# ai.net
KiCad netlist of a schematic drawn in Altium Designer
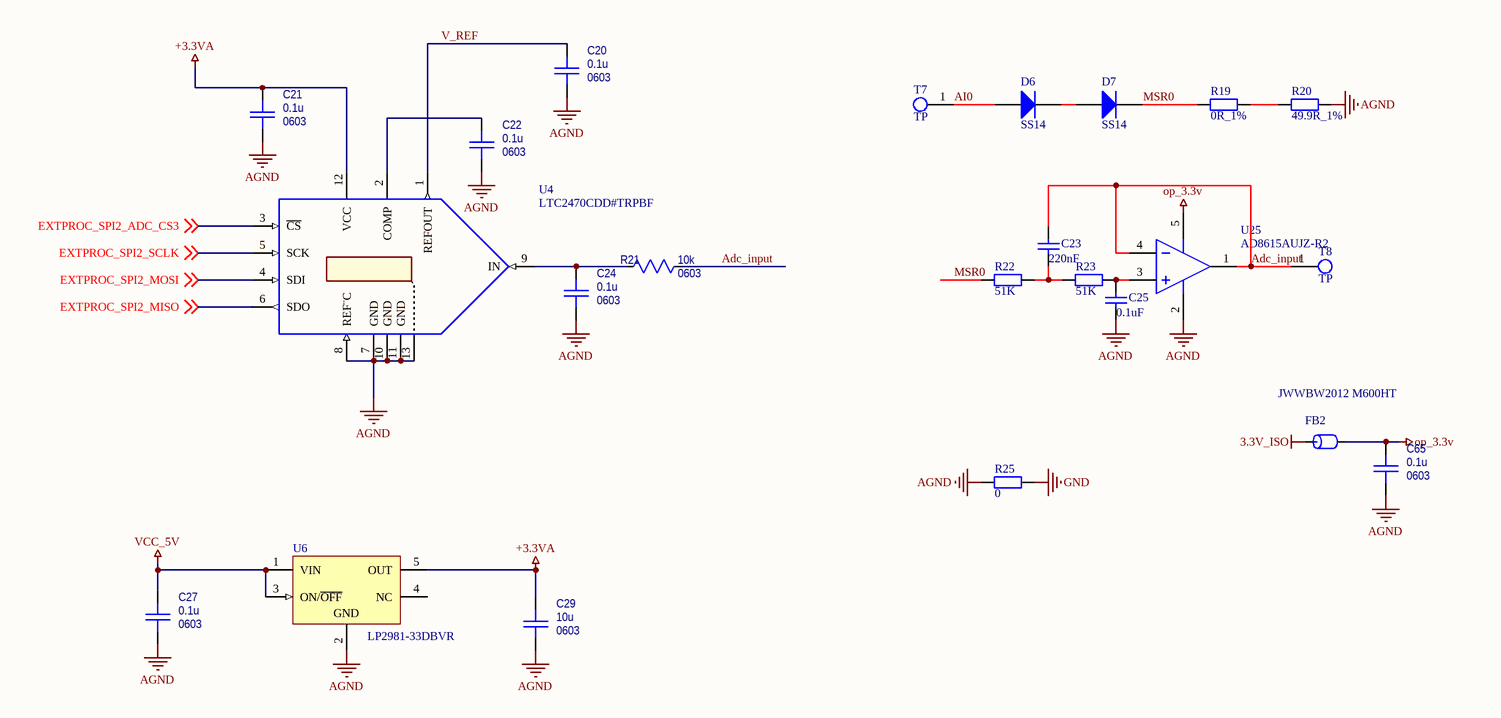
[diagram p0: ai.SchDoc]

(export (version "E")
  (design (tool "Eeschema 10.0.6"))
  (components
    (comp (ref "C20")
      (value "0.1u")
      (footprint "CAPC1608X092N_0603")
      (description "Capacitor, MLCC")
      (fields
        (field (name "PARTNUMBER") "C0603C104M5RACTU")
        (field (name "TOLERANCE") "[tol]")
        (field (name "PACKAGE") "0603")
      )
      (libsource (lib "Karl") (part "Capacitor_0603"))
    )
    (comp (ref "C21")
      (value "0.1u")
      (footprint "CAPC1608X092N_0603")
      (description "Capacitor, MLCC")
      (fields
        (field (name "PARTNUMBER") "C0603C104M5RACTU")
        (field (name "TOLERANCE") "[tol]")
        (field (name "PACKAGE") "0603")
      )
      (libsource (lib "Karl") (part "Capacitor_0603"))
    )
    (comp (ref "C22")
      (value "0.1u")
      (footprint "CAPC1608X092N_0603")
      (description "Capacitor, MLCC")
      (fields
        (field (name "PARTNUMBER") "C0603C104M5RACTU")
        (field (name "TOLERANCE") "[tol]")
        (field (name "PACKAGE") "0603")
      )
      (libsource (lib "Karl") (part "Capacitor_0603"))
    )
    (comp (ref "C23")
      (value "220nF")
      (footprint "0805C")
      (description "Capacitor")
      (fields (field (name "PUBLISHER") "Altium Limited"))
      (libsource (lib "Miscellaneous Devices") (part "Cap"))
    )
    (comp (ref "C24")
      (value "0.1u")
      (footprint "CAPC1608X092N_0603")
      (description "Capacitor, MLCC")
      (fields
        (field (name "PARTNUMBER") "C0603C104M5RACTU")
        (field (name "TOLERANCE") "[tol]")
        (field (name "PACKAGE") "0603")
      )
      (libsource (lib "Karl") (part "Capacitor_0603"))
    )
    (comp (ref "C25")
      (value "0.1uF")
      (footprint "0603C")
      (description "Capacitor")
      (fields (field (name "PUBLISHER") "Altium Limited"))
      (libsource (lib "Miscellaneous Devices") (part "Cap"))
    )
    (comp (ref "C27")
      (value "0.1u")
      (footprint "CAPC1608X092N_0603")
      (description "Capacitor, MLCC")
      (fields
        (field (name "PARTNUMBER") "C0603C104M5RACTU")
        (field (name "TOLERANCE") "[tol]")
        (field (name "PACKAGE") "0603")
      )
      (libsource (lib "Karl") (part "Capacitor_0603"))
    )
    (comp (ref "C29")
      (value "10u")
      (footprint "CAPC1608X092N_0603")
      (description "Capacitor, MLCC")
      (fields
        (field (name "PARTNUMBER") "GRM188R61A106KE69D")
        (field (name "TOLERANCE") "[tol]")
        (field (name "PACKAGE") "0603")
      )
      (libsource (lib "Karl") (part "Capacitor_0603"))
    )
    (comp (ref "C65")
      (value "0.1u")
      (footprint "CAPC1608X092N_0603")
      (description "Capacitor, MLCC")
      (fields
        (field (name "PARTNUMBER") "C0603C104M5RACTU")
        (field (name "TOLERANCE") "[tol]")
        (field (name "PACKAGE") "0603")
      )
      (libsource (lib "Karl") (part "Capacitor_0603"))
    )
    (comp (ref "D6")
      (value "SS14")
      (footprint "DO-214AC")
      (description "Default Diode")
      (fields (field (name "PUBLISHER") "Altium Limited"))
      (libsource (lib "Miscellaneous Devices") (part "Diode"))
    )
    (comp (ref "D7")
      (value "SS14")
      (footprint "DO-214AC")
      (description "Default Diode")
      (fields (field (name "PUBLISHER") "Altium Limited"))
      (libsource (lib "Miscellaneous Devices") (part "Diode"))
    )
    (comp (ref "FB2")
      (value "JWWBW2012 M600HT")
      (footprint "0805R")
      (libsource (lib "Schlib_20110825") (part "FB"))
    )
    (comp (ref "R19") (value "0R_1%") (footprint "0805R") (libsource (lib "MQlibrary") (part "Res0805M")))
    (comp (ref "R20") (value "49.9R_1%") (footprint "0805R") (libsource (lib "MQlibrary") (part "Res0805M")))
    (comp (ref "R21")
      (value "10k")
      (footprint "RESC1608X055N_0603")
      (description "Resistor, Standard")
      (fields
        (field (name "PARTNUMBER") "RR0816P-103-D")
        (field (name "TOLERANCE") "tol")
        (field (name "PACKAGE") "0603")
      )
      (libsource (lib "Karl") (part "Resistor_0603"))
    )
    (comp (ref "R22") (value "51K") (footprint "0603R") (libsource (lib "MQlibrary") (part "Res0805M")))
    (comp (ref "R23") (value "51K") (footprint "0603R") (libsource (lib "MQlibrary") (part "Res0805M")))
    (comp (ref "R25") (value "0") (footprint "1206R") (libsource (lib "MQlibrary") (part "Res0805M")))
    (comp (ref "T7") (value "TP") (footprint "TPD") (libsource (lib "Schlib_20110825") (part "TP")))
    (comp (ref "T8") (value "TP") (footprint "TPD") (libsource (lib "Schlib_20110825") (part "TP")))
    (comp (ref "U4")
      (value "LTC2470CDD#TRPBF")
      (footprint "LT-DD-12_V")
      (description "16-bit Analog-to-digital Converters, 12-pin SON (DD-12), 0 to 70 degC, Pb-Free, Tape and Reel")
      (libsource (lib "Bogen") (part "LTC2470CDD#TRPBF"))
    )
    (comp (ref "U6")
      (value "LP2981-33DBVR")
      (footprint "DBV0005A_M")
      (description "Micropower 100 mA Ultra Low-Dropout Regulator, 5-pin SOT-23, Pb-Free")
      (libsource (lib "Bogen") (part "LP2981-33DBVR"))
    )
    (comp (ref "U25")
      (value "AD8615AUJZ-R2")
      (footprint "sot-23-5")
      (libsource (lib "Schlib_20110825") (part "AD8615"))
    )
  )
  (nets
    (net (code "1") (name "+3.3VA") (class "Default")
      (node (ref "C21") (pin "1") (pinfunction "1_1") (pintype "passive"))
      (node (ref "C29") (pin "1") (pinfunction "1_1") (pintype "passive"))
      (node (ref "U4") (pin "12") (pinfunction "VCC_12") (pintype "power_in"))
      (node (ref "U6") (pin "5") (pinfunction "OUT_5") (pintype "power_in"))
    )
    (net (code "2") (name "/AI0") (class "Default")
      (node (ref "D6") (pin "1") (pinfunction "A_1") (pintype "passive"))
      (node (ref "T7") (pin "1") (pintype "passive"))
    )
    (net (code "3") (name "/Adc_input") (class "Default")
      (node (ref "C23") (pin "2") (pinfunction "2_2") (pintype "passive"))
      (node (ref "R21") (pin "1") (pinfunction "1_1") (pintype "passive"))
      (node (ref "T8") (pin "1") (pintype "passive"))
      (node (ref "U25") (pin "1") (pinfunction "OS_NUL_1") (pintype "passive"))
      (node (ref "U25") (pin "4") (pinfunction "V-_4") (pintype "power_in"))
    )
    (net (code "4") (name "/MSR0") (class "Default")
      (node (ref "D7") (pin "2") (pinfunction "K_2") (pintype "passive"))
      (node (ref "R19") (pin "2") (pinfunction "2_2") (pintype "passive"))
      (node (ref "R22") (pin "2") (pinfunction "2_2") (pintype "passive"))
    )
    (net (code "5") (name "/V_REF") (class "Default")
      (node (ref "C20") (pin "1") (pinfunction "1_1") (pintype "passive"))
      (node (ref "U4") (pin "1") (pinfunction "REFOUT_1") (pintype "output"))
    )
    (net (code "6") (name "3.3V_ISO") (class "Default") (node (ref "FB2") (pin "1") (pintype "passive")))
    (net (code "7") (name "AGND") (class "Default")
      (node (ref "C20") (pin "2") (pinfunction "2_2") (pintype "passive"))
      (node (ref "C21") (pin "2") (pinfunction "2_2") (pintype "passive"))
      (node (ref "C22") (pin "2") (pinfunction "2_2") (pintype "passive"))
      (node (ref "C24") (pin "2") (pinfunction "2_2") (pintype "passive"))
      (node (ref "C25") (pin "1") (pinfunction "1_1") (pintype "passive"))
      (node (ref "C27") (pin "2") (pinfunction "2_2") (pintype "passive"))
      (node (ref "C29") (pin "2") (pinfunction "2_2") (pintype "passive"))
      (node (ref "C65") (pin "2") (pinfunction "2_2") (pintype "passive"))
      (node (ref "R20") (pin "1") (pinfunction "1_1") (pintype "passive"))
      (node (ref "R25") (pin "2") (pinfunction "2_2") (pintype "passive"))
      (node (ref "U25") (pin "2") (pinfunction "G_2") (pintype "power_in"))
      (node (ref "U4") (pin "10") (pinfunction "GND_10") (pintype "power_in"))
      (node (ref "U4") (pin "11") (pinfunction "GND_11") (pintype "power_in"))
      (node (ref "U4") (pin "13") (pinfunction "EP_13") (pintype "power_in"))
      (node (ref "U4") (pin "7") (pinfunction "GND_7") (pintype "power_in"))
      (node (ref "U4") (pin "8") (pinfunction "REF¨C_8") (pintype "input"))
      (node (ref "U6") (pin "2") (pinfunction "GND_2") (pintype "power_in"))
    )
    (net (code "8") (name "EXTPROC_SPI2_ADC_CS3") (class "Default")
      (node (ref "U4") (pin "3") (pinfunction "~{CS}_3") (pintype "input"))
    )
    (net (code "9") (name "EXTPROC_SPI2_MISO") (class "Default")
      (node (ref "U4") (pin "6") (pinfunction "SDO_6") (pintype "output"))
    )
    (net (code "10") (name "EXTPROC_SPI2_MOSI") (class "Default")
      (node (ref "U4") (pin "4") (pinfunction "SDI_4") (pintype "input"))
    )
    (net (code "11") (name "EXTPROC_SPI2_SCLK") (class "Default")
      (node (ref "U4") (pin "5") (pinfunction "SCK_5") (pintype "input"))
    )
    (net (code "12") (name "GND") (class "Default")
      (node (ref "R25") (pin "1") (pinfunction "1_1") (pintype "passive"))
    )
    (net (code "13") (name "Net-(C23-Pad1)") (class "Default")
      (node (ref "C23") (pin "1") (pinfunction "1_1") (pintype "passive"))
      (node (ref "R22") (pin "1") (pinfunction "1_1") (pintype "passive"))
      (node (ref "R23") (pin "2") (pinfunction "2_2") (pintype "passive"))
    )
    (net (code "14") (name "Net-(D6-K)") (class "Default")
      (node (ref "D6") (pin "2") (pinfunction "K_2") (pintype "passive"))
      (node (ref "D7") (pin "1") (pinfunction "A_1") (pintype "passive"))
    )
    (net (code "15") (name "Net-(R19-Pad1)") (class "Default")
      (node (ref "R19") (pin "1") (pinfunction "1_1") (pintype "passive"))
      (node (ref "R20") (pin "2") (pinfunction "2_2") (pintype "passive"))
    )
    (net (code "16") (name "Net-(U4-COMP)") (class "Default")
      (node (ref "C22") (pin "1") (pinfunction "1_1") (pintype "passive"))
      (node (ref "U4") (pin "2") (pinfunction "COMP_2") (pintype "passive"))
    )
    (net (code "17") (name "Net-(U4-IN)") (class "Default")
      (node (ref "C24") (pin "1") (pinfunction "1_1") (pintype "passive"))
      (node (ref "R21") (pin "2") (pinfunction "2_2") (pintype "passive"))
      (node (ref "U4") (pin "9") (pinfunction "IN_9") (pintype "input"))
    )
    (net (code "18") (name "Net-(U25-V+)") (class "Default")
      (node (ref "C25") (pin "2") (pinfunction "2_2") (pintype "passive"))
      (node (ref "R23") (pin "1") (pinfunction "1_1") (pintype "passive"))
      (node (ref "U25") (pin "3") (pinfunction "V+_3") (pintype "power_in"))
    )
    (net (code "19") (name "VCC_5V") (class "Default")
      (node (ref "C27") (pin "1") (pinfunction "1_1") (pintype "passive"))
      (node (ref "U6") (pin "1") (pinfunction "VIN_1") (pintype "power_in"))
      (node (ref "U6") (pin "3") (pinfunction "ON/~{OFF}_3") (pintype "input"))
    )
    (net (code "20") (name "op_3.3v") (class "Default")
      (node (ref "C65") (pin "1") (pinfunction "1_1") (pintype "passive"))
      (node (ref "FB2") (pin "2") (pintype "passive"))
      (node (ref "U25") (pin "5") (pinfunction "VCC_5") (pintype "passive"))
    )
    (net (code "21") (name "unconnected-(U6-NC-Pad4)") (class "Default")
      (node (ref "U6") (pin "4") (pinfunction "NC_4") (pintype "passive"))
    )
  )
)
